# Logic_buffer.net
KiCad netlist of a schematic drawn in Altium Designer
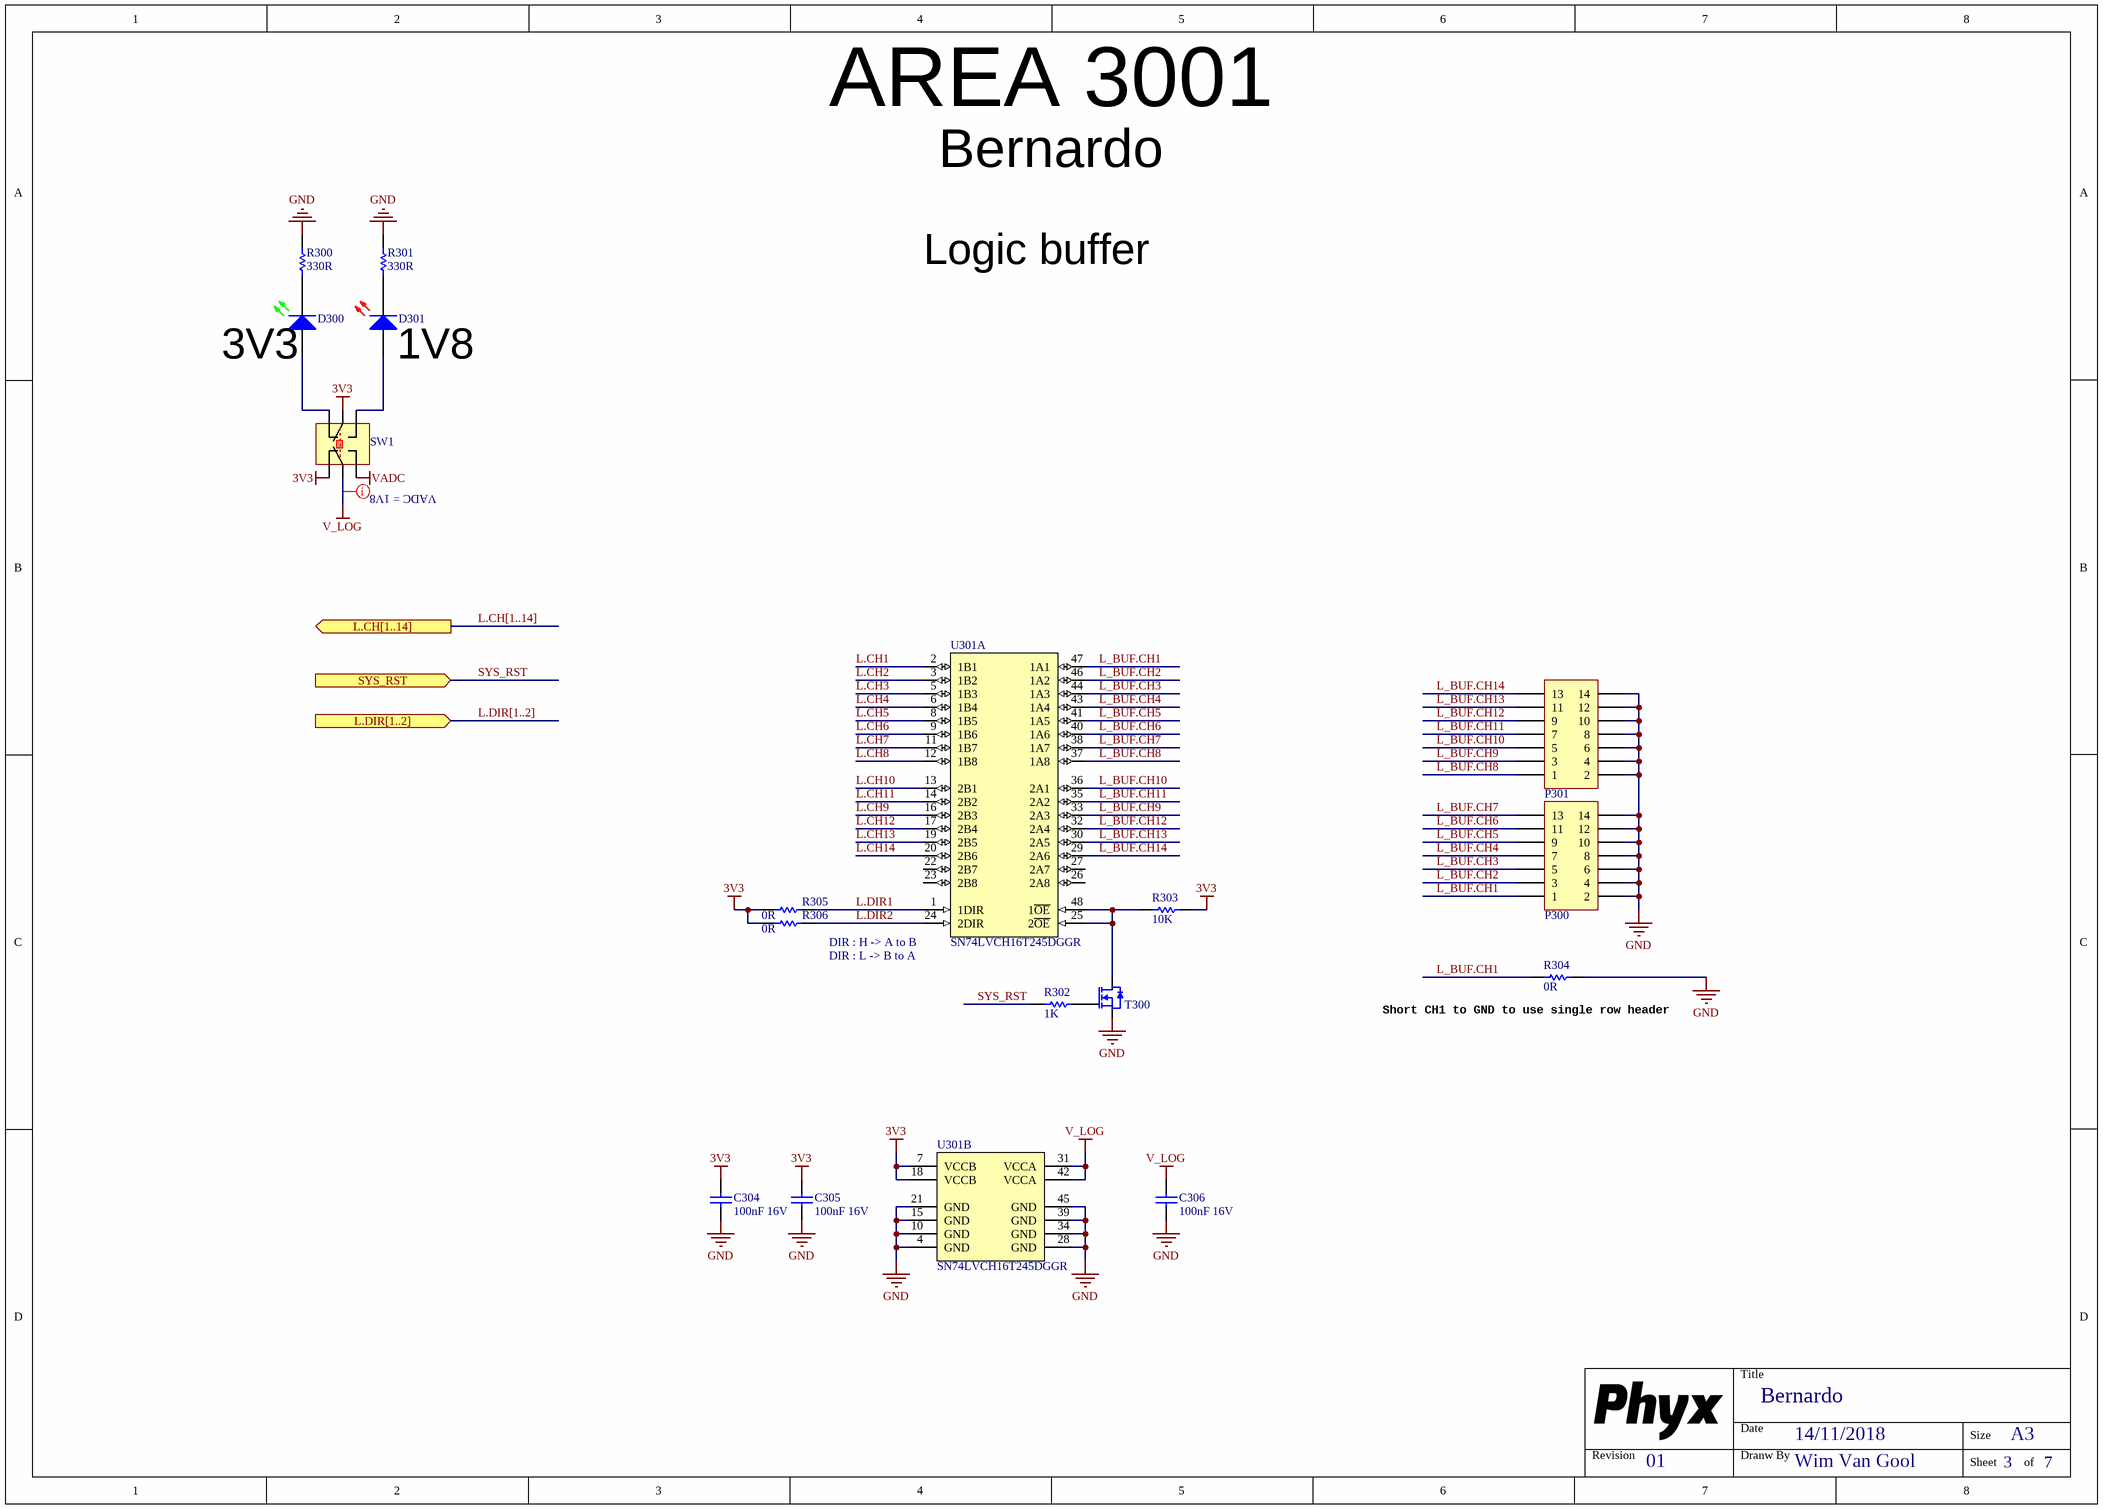
[diagram p0: Logic_buffer.SchDoc]

(export (version "E")
  (design (tool "Eeschema 10.0.6"))
  (components
    (comp (ref "C304")
      (value "100nF 16V")
      (footprint "C0603_N")
      (description "Capacitor Ceramic")
      (fields (field (name "Comment") "CAP_CERAMIC"))
      (libsource (lib "Phyx_Components") (part "CAP_CERAMIC"))
    )
    (comp (ref "C305")
      (value "100nF 16V")
      (footprint "C0603_N")
      (description "Capacitor Ceramic")
      (fields (field (name "Comment") "CAP_CERAMIC"))
      (libsource (lib "Phyx_Components") (part "CAP_CERAMIC"))
    )
    (comp (ref "C306")
      (value "100nF 16V")
      (footprint "C0603_N")
      (description "Capacitor Ceramic")
      (fields (field (name "Comment") "CAP_CERAMIC"))
      (libsource (lib "Phyx_Components") (part "CAP_CERAMIC"))
    )
    (comp (ref "D300")
      (value "Default 0805 Green LED")
      (footprint "LED_0805_GR")
      (description "=Description")
      (libsource (lib "Phyx_Components") (part "LED_GREEN"))
    )
    (comp (ref "D301")
      (value "Default 0805 Red LED")
      (footprint "LED_0805_RD")
      (description "=Description")
      (libsource (lib "Phyx_Components") (part "LED_RED"))
    )
    (comp (ref "P300")
      (value "Header 7X2")
      (footprint "HDR2X7")
      (libsource (lib "Phyx_Components") (part "Header 7X2"))
    )
    (comp (ref "P301")
      (value "Header 7X2")
      (footprint "HDR2X7")
      (libsource (lib "Phyx_Components") (part "Header 7X2"))
    )
    (comp (ref "R300")
      (value "330R")
      (footprint "R0603_N")
      (fields (field (name "Comment") "RESISTOR"))
      (libsource (lib "Phyx_Components") (part "RESISTOR"))
    )
    (comp (ref "R301")
      (value "330R")
      (footprint "R0603_N")
      (fields (field (name "Comment") "RESISTOR"))
      (libsource (lib "Phyx_Components") (part "RESISTOR"))
    )
    (comp (ref "R302")
      (value "1K")
      (footprint "R0603_N")
      (fields (field (name "Comment") "RESISTOR"))
      (libsource (lib "Phyx_Components") (part "RESISTOR"))
    )
    (comp (ref "R303")
      (value "10K")
      (footprint "R0603_N")
      (fields (field (name "Comment") "RESISTOR"))
      (libsource (lib "Phyx_Components") (part "RESISTOR"))
    )
    (comp (ref "R304")
      (value "0R")
      (footprint "R0603_N")
      (fields (field (name "Comment") "RESISTOR"))
      (libsource (lib "Phyx_Components") (part "RESISTOR"))
    )
    (comp (ref "R305")
      (value "0R")
      (footprint "R0603_N")
      (fields (field (name "Comment") "RESISTOR"))
      (libsource (lib "Phyx_Components") (part "RESISTOR"))
    )
    (comp (ref "R306")
      (value "0R")
      (footprint "R0603_N")
      (fields (field (name "Comment") "RESISTOR"))
      (libsource (lib "Phyx_Components") (part "RESISTOR"))
    )
    (comp (ref "SW1")
      (value "mini Switch 2 pole double throw straight 50V 0.3A")
      (footprint "SS22D07")
      (libsource (lib "Phyx_Components") (part "SW_2P2T"))
    )
    (comp (ref "T300")
      (value "0.2A N-Ch MOSFET Vgs 3.2")
      (footprint "SOT23-3")
      (libsource (lib "Phyx_Components") (part "N_MOSFET_GSD"))
    )
    (comp (ref "U301")
      (value "SN74LVCH16T245DGGR")
      (footprint "TI_DGG_R-PDSO-G48")
      (description "=Description")
      (fields
        (field (name "Comment") "SN74LVCH16T245DGGR  Bus Transceiver LVC 16Ch 32 mA 6 ns 1V65 to 5V5 TSSOP48")
      )
      (libsource (lib "Phyx_Components") (part "SN74LVCH16T245_SOP"))
    )
  )
  (nets
    (net (code "1") (name "/L.CH1") (class "Default")
      (node (ref "U301") (pin "2") (pinfunction "1B1_2") (pintype "bidirectional"))
    )
    (net (code "2") (name "/L.CH2") (class "Default")
      (node (ref "U301") (pin "3") (pinfunction "1B2_3") (pintype "bidirectional"))
    )
    (net (code "3") (name "/L.CH3") (class "Default")
      (node (ref "U301") (pin "5") (pinfunction "1B3_5") (pintype "bidirectional"))
    )
    (net (code "4") (name "/L.CH4") (class "Default")
      (node (ref "U301") (pin "6") (pinfunction "1B4_6") (pintype "bidirectional"))
    )
    (net (code "5") (name "/L.CH5") (class "Default")
      (node (ref "U301") (pin "8") (pinfunction "1B5_8") (pintype "bidirectional"))
    )
    (net (code "6") (name "/L.CH6") (class "Default")
      (node (ref "U301") (pin "9") (pinfunction "1B6_9") (pintype "bidirectional"))
    )
    (net (code "7") (name "/L.CH7") (class "Default")
      (node (ref "U301") (pin "11") (pinfunction "1B7_11") (pintype "bidirectional"))
    )
    (net (code "8") (name "/L.CH8") (class "Default")
      (node (ref "U301") (pin "12") (pinfunction "1B8_12") (pintype "bidirectional"))
    )
    (net (code "9") (name "/L.CH9") (class "Default")
      (node (ref "U301") (pin "16") (pinfunction "2B3_16") (pintype "bidirectional"))
    )
    (net (code "10") (name "/L.CH10") (class "Default")
      (node (ref "U301") (pin "13") (pinfunction "2B1_13") (pintype "bidirectional"))
    )
    (net (code "11") (name "/L.CH11") (class "Default")
      (node (ref "U301") (pin "14") (pinfunction "2B2_14") (pintype "bidirectional"))
    )
    (net (code "12") (name "/L.CH12") (class "Default")
      (node (ref "U301") (pin "17") (pinfunction "2B4_17") (pintype "bidirectional"))
    )
    (net (code "13") (name "/L.CH13") (class "Default")
      (node (ref "U301") (pin "19") (pinfunction "2B5_19") (pintype "bidirectional"))
    )
    (net (code "14") (name "/L.CH14") (class "Default")
      (node (ref "U301") (pin "20") (pinfunction "2B6_20") (pintype "bidirectional"))
    )
    (net (code "16") (name "/L.DIR1") (class "Default")
      (node (ref "R305") (pin "1") (pinfunction "1_1") (pintype "passive"))
      (node (ref "U301") (pin "1") (pinfunction "1DIR_1") (pintype "input"))
    )
    (net (code "17") (name "/L.DIR2") (class "Default")
      (node (ref "R306") (pin "1") (pinfunction "1_1") (pintype "passive"))
      (node (ref "U301") (pin "24") (pinfunction "2DIR_24") (pintype "input"))
    )
    (net (code "19") (name "/L_BUF.CH1") (class "Default")
      (node (ref "P300") (pin "1") (pinfunction "1_1") (pintype "passive"))
      (node (ref "R304") (pin "2") (pinfunction "2_2") (pintype "passive"))
      (node (ref "U301") (pin "47") (pinfunction "1A1_47") (pintype "bidirectional"))
    )
    (net (code "20") (name "/L_BUF.CH2") (class "Default")
      (node (ref "P300") (pin "3") (pinfunction "3_3") (pintype "passive"))
      (node (ref "U301") (pin "46") (pinfunction "1A2_46") (pintype "bidirectional"))
    )
    (net (code "21") (name "/L_BUF.CH3") (class "Default")
      (node (ref "P300") (pin "5") (pinfunction "5_5") (pintype "passive"))
      (node (ref "U301") (pin "44") (pinfunction "1A3_44") (pintype "bidirectional"))
    )
    (net (code "22") (name "/L_BUF.CH4") (class "Default")
      (node (ref "P300") (pin "7") (pinfunction "7_7") (pintype "passive"))
      (node (ref "U301") (pin "43") (pinfunction "1A4_43") (pintype "bidirectional"))
    )
    (net (code "23") (name "/L_BUF.CH5") (class "Default")
      (node (ref "P300") (pin "9") (pinfunction "9_9") (pintype "passive"))
      (node (ref "U301") (pin "41") (pinfunction "1A5_41") (pintype "bidirectional"))
    )
    (net (code "24") (name "/L_BUF.CH6") (class "Default")
      (node (ref "P300") (pin "11") (pinfunction "11_11") (pintype "passive"))
      (node (ref "U301") (pin "40") (pinfunction "1A6_40") (pintype "bidirectional"))
    )
    (net (code "25") (name "/L_BUF.CH7") (class "Default")
      (node (ref "P300") (pin "13") (pinfunction "13_13") (pintype "passive"))
      (node (ref "U301") (pin "38") (pinfunction "1A7_38") (pintype "bidirectional"))
    )
    (net (code "26") (name "/L_BUF.CH8") (class "Default")
      (node (ref "P301") (pin "1") (pinfunction "1_1") (pintype "passive"))
      (node (ref "U301") (pin "37") (pinfunction "1A8_37") (pintype "bidirectional"))
    )
    (net (code "27") (name "/L_BUF.CH9") (class "Default")
      (node (ref "P301") (pin "3") (pinfunction "3_3") (pintype "passive"))
      (node (ref "U301") (pin "33") (pinfunction "2A3_33") (pintype "bidirectional"))
    )
    (net (code "28") (name "/L_BUF.CH10") (class "Default")
      (node (ref "P301") (pin "5") (pinfunction "5_5") (pintype "passive"))
      (node (ref "U301") (pin "36") (pinfunction "2A1_36") (pintype "bidirectional"))
    )
    (net (code "29") (name "/L_BUF.CH11") (class "Default")
      (node (ref "P301") (pin "7") (pinfunction "7_7") (pintype "passive"))
      (node (ref "U301") (pin "35") (pinfunction "2A2_35") (pintype "bidirectional"))
    )
    (net (code "30") (name "/L_BUF.CH12") (class "Default")
      (node (ref "P301") (pin "9") (pinfunction "9_9") (pintype "passive"))
      (node (ref "U301") (pin "32") (pinfunction "2A4_32") (pintype "bidirectional"))
    )
    (net (code "31") (name "/L_BUF.CH13") (class "Default")
      (node (ref "P301") (pin "11") (pinfunction "11_11") (pintype "passive"))
      (node (ref "U301") (pin "30") (pinfunction "2A5_30") (pintype "bidirectional"))
    )
    (net (code "32") (name "/L_BUF.CH14") (class "Default")
      (node (ref "P301") (pin "13") (pinfunction "13_13") (pintype "passive"))
      (node (ref "U301") (pin "29") (pinfunction "2A6_29") (pintype "bidirectional"))
    )
    (net (code "33") (name "/SYS_RST") (class "Default")
      (node (ref "R302") (pin "2") (pinfunction "2_2") (pintype "passive"))
    )
    (net (code "34") (name "3V3") (class "Default")
      (node (ref "C304") (pin "1") (pinfunction "1_1") (pintype "passive"))
      (node (ref "C305") (pin "1") (pinfunction "1_1") (pintype "passive"))
      (node (ref "R303") (pin "1") (pinfunction "1_1") (pintype "passive"))
      (node (ref "R305") (pin "2") (pinfunction "2_2") (pintype "passive"))
      (node (ref "R306") (pin "2") (pinfunction "2_2") (pintype "passive"))
      (node (ref "SW1") (pin "2") (pinfunction "2_2") (pintype "passive"))
      (node (ref "SW1") (pin "3") (pinfunction "3_3") (pintype "passive"))
      (node (ref "U301") (pin "18") (pinfunction "VCCB_18") (pintype "power_in"))
      (node (ref "U301") (pin "7") (pinfunction "VCCB_7") (pintype "power_in"))
    )
    (net (code "35") (name "GND") (class "Default")
      (node (ref "C304") (pin "2") (pinfunction "2_2") (pintype "passive"))
      (node (ref "C305") (pin "2") (pinfunction "2_2") (pintype "passive"))
      (node (ref "C306") (pin "2") (pinfunction "2_2") (pintype "passive"))
      (node (ref "P300") (pin "10") (pinfunction "10_10") (pintype "passive"))
      (node (ref "P300") (pin "12") (pinfunction "12_12") (pintype "passive"))
      (node (ref "P300") (pin "14") (pinfunction "14_14") (pintype "passive"))
      (node (ref "P300") (pin "2") (pinfunction "2_2") (pintype "passive"))
      (node (ref "P300") (pin "4") (pinfunction "4_4") (pintype "passive"))
      (node (ref "P300") (pin "6") (pinfunction "6_6") (pintype "passive"))
      (node (ref "P300") (pin "8") (pinfunction "8_8") (pintype "passive"))
      (node (ref "P301") (pin "10") (pinfunction "10_10") (pintype "passive"))
      (node (ref "P301") (pin "12") (pinfunction "12_12") (pintype "passive"))
      (node (ref "P301") (pin "14") (pinfunction "14_14") (pintype "passive"))
      (node (ref "P301") (pin "2") (pinfunction "2_2") (pintype "passive"))
      (node (ref "P301") (pin "4") (pinfunction "4_4") (pintype "passive"))
      (node (ref "P301") (pin "6") (pinfunction "6_6") (pintype "passive"))
      (node (ref "P301") (pin "8") (pinfunction "8_8") (pintype "passive"))
      (node (ref "R300") (pin "1") (pinfunction "1_1") (pintype "passive"))
      (node (ref "R301") (pin "1") (pinfunction "1_1") (pintype "passive"))
      (node (ref "R304") (pin "1") (pinfunction "1_1") (pintype "passive"))
      (node (ref "T300") (pin "2") (pinfunction "S_2") (pintype "passive"))
      (node (ref "U301") (pin "10") (pinfunction "GND_10") (pintype "power_in"))
      (node (ref "U301") (pin "15") (pinfunction "GND_15") (pintype "power_in"))
      (node (ref "U301") (pin "21") (pinfunction "GND_21") (pintype "power_in"))
      (node (ref "U301") (pin "28") (pinfunction "GND_28") (pintype "power_in"))
      (node (ref "U301") (pin "34") (pinfunction "GND_34") (pintype "power_in"))
      (node (ref "U301") (pin "39") (pinfunction "GND_39") (pintype "power_in"))
      (node (ref "U301") (pin "4") (pinfunction "GND_4") (pintype "power_in"))
      (node (ref "U301") (pin "45") (pinfunction "GND_45") (pintype "power_in"))
    )
    (net (code "36") (name "Net-(D300-A)") (class "Default")
      (node (ref "D300") (pin "1") (pinfunction "A_1") (pintype "passive"))
      (node (ref "SW1") (pin "1") (pinfunction "1_1") (pintype "passive"))
    )
    (net (code "37") (name "Net-(D300-K)") (class "Default")
      (node (ref "D300") (pin "2") (pinfunction "K_2") (pintype "passive"))
      (node (ref "R300") (pin "2") (pinfunction "2_2") (pintype "passive"))
    )
    (net (code "38") (name "Net-(D301-A)") (class "Default")
      (node (ref "D301") (pin "1") (pinfunction "A_1") (pintype "passive"))
      (node (ref "SW1") (pin "5") (pinfunction "5_5") (pintype "passive"))
    )
    (net (code "39") (name "Net-(D301-K)") (class "Default")
      (node (ref "D301") (pin "2") (pinfunction "K_2") (pintype "passive"))
      (node (ref "R301") (pin "2") (pinfunction "2_2") (pintype "passive"))
    )
    (net (code "40") (name "Net-(T300-D)") (class "Default")
      (node (ref "R303") (pin "2") (pinfunction "2_2") (pintype "passive"))
      (node (ref "T300") (pin "3") (pinfunction "D_3") (pintype "passive"))
      (node (ref "U301") (pin "25") (pinfunction "2~{OE}_25") (pintype "input"))
      (node (ref "U301") (pin "48") (pinfunction "1~{OE}_48") (pintype "input"))
    )
    (net (code "41") (name "Net-(T300-G)") (class "Default")
      (node (ref "R302") (pin "1") (pinfunction "1_1") (pintype "passive"))
      (node (ref "T300") (pin "1") (pinfunction "G_1") (pintype "passive"))
    )
    (net (code "42") (name "VADC") (class "Default")
      (node (ref "SW1") (pin "6") (pinfunction "5_6") (pintype "passive"))
    )
    (net (code "43") (name "V_LOG") (class "Default")
      (node (ref "C306") (pin "1") (pinfunction "1_1") (pintype "passive"))
      (node (ref "SW1") (pin "4") (pinfunction "4_4") (pintype "passive"))
      (node (ref "U301") (pin "31") (pinfunction "VCCA_31") (pintype "power_in"))
      (node (ref "U301") (pin "42") (pinfunction "VCCA_42") (pintype "power_in"))
    )
    (net (code "44") (name "unconnected-(U301A-2A7-Pad27)") (class "Default")
      (node (ref "U301") (pin "27") (pinfunction "2A7_27") (pintype "bidirectional"))
    )
    (net (code "45") (name "unconnected-(U301A-2A8-Pad26)") (class "Default")
      (node (ref "U301") (pin "26") (pinfunction "2A8_26") (pintype "bidirectional"))
    )
    (net (code "46") (name "unconnected-(U301A-2B7-Pad22)") (class "Default")
      (node (ref "U301") (pin "22") (pinfunction "2B7_22") (pintype "bidirectional"))
    )
    (net (code "47") (name "unconnected-(U301A-2B8-Pad23)") (class "Default")
      (node (ref "U301") (pin "23") (pinfunction "2B8_23") (pintype "bidirectional"))
    )
  )
)
